# Programmer_Board_v1.net
KiCad netlist of a schematic drawn in EAGLE
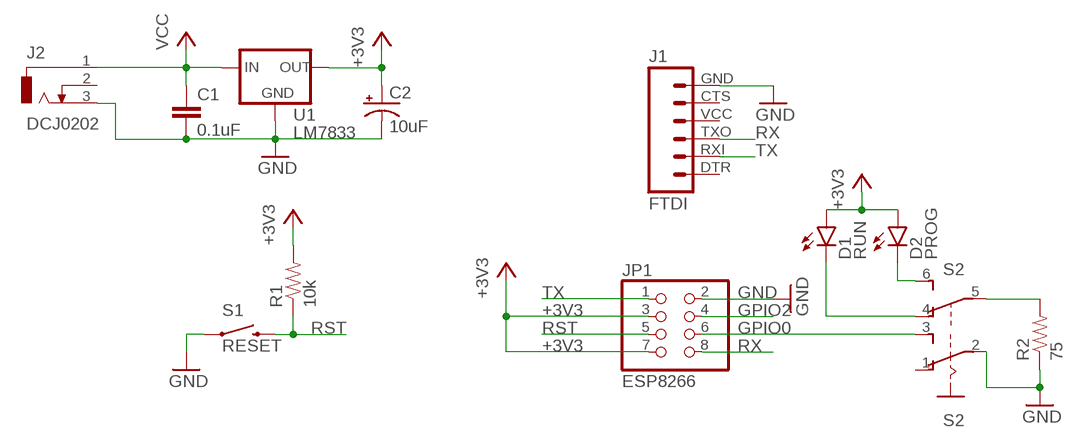
[diagram p0: schematic, sheet 1]

(export (version "E")
  (design (tool "Eeschema 10.0.6"))
  (components
    (comp (ref "C1")
      (value "0.1uF")
      (footprint "eagle-import:CAP-PTH-SMALL-KIT")
      (libsource (lib "eagle-import") (part "0.1UF-50V-20%(PTH)KIT-EZ"))
    )
    (comp (ref "C2")
      (value "10uF")
      (footprint "eagle-import:CPOL-RADIAL-10UF-25V-KIT")
      (libsource (lib "eagle-import") (part "10UF-25V-20%(PTH)KIT"))
    )
    (comp (ref "D1")
      (value "RUN")
      (footprint "eagle-import:LED3MM")
      (libsource (lib "eagle-import") (part "LED3MM"))
    )
    (comp (ref "D2")
      (value "PROG")
      (footprint "eagle-import:LED3MM")
      (libsource (lib "eagle-import") (part "LED3MM"))
    )
    (comp (ref "J1")
      (value "FTDI")
      (footprint "eagle-import:FTDI_BASIC")
      (libsource (lib "eagle-import") (part "FTDI_BASICPTH"))
    )
    (comp (ref "J2")
      (value "DCJ0202")
      (footprint "eagle-import:DCJ0202")
      (libsource (lib "eagle-import") (part "DCJ0202"))
    )
    (comp (ref "JP1")
      (value "ESP8266")
      (footprint "eagle-import:2X04")
      (libsource (lib "eagle-import") (part "PINHD-2X4"))
    )
    (comp (ref "R1")
      (value "10k")
      (footprint "eagle-import:AXIAL-0.3")
      (libsource (lib "eagle-import") (part "10KOHM-1/4W-1%(PTH)HORIZ"))
    )
    (comp (ref "R2")
      (value "75")
      (footprint "eagle-import:AXIAL-0.3")
      (libsource (lib "eagle-import") (part "10KOHM-1/4W-1%(PTH)HORIZ"))
    )
    (comp (ref "S1")
      (value "RESET")
      (footprint "eagle-import:TACTILE-PTH")
      (libsource (lib "eagle-import") (part "SWITCH-MOMENTARY-2PTH"))
    )
    (comp (ref "S2")
      (value "A68-A31")
      (footprint "eagle-import:A68-A31")
      (libsource (lib "eagle-import") (part "A68-A31"))
    )
    (comp (ref "U1")
      (value "LM7833")
      (footprint "eagle-import:TO-220-ALT")
      (libsource (lib "eagle-import") (part "V_REG_78XX-TO-220"))
    )
  )
  (nets
    (net (code "1") (name "+3V3") (class "Default")
      (node (ref "C2") (pin "1") (pinfunction "+_1") (pintype "passive"))
      (node (ref "D1") (pin "A") (pinfunction "A_A") (pintype "passive"))
      (node (ref "D2") (pin "A") (pinfunction "A_A") (pintype "passive"))
      (node (ref "JP1") (pin "3") (pinfunction "3_3") (pintype "passive"))
      (node (ref "JP1") (pin "7") (pinfunction "7_7") (pintype "passive"))
      (node (ref "R1") (pin "P$2") (pinfunction "2_P$2") (pintype "passive"))
      (node (ref "U1") (pin "OUT") (pinfunction "OUT_OUT") (pintype "passive"))
    )
    (net (code "2") (name "/GPIO0") (class "Default")
      (node (ref "JP1") (pin "6") (pinfunction "6_6") (pintype "passive"))
      (node (ref "S2") (pin "3") (pinfunction "S_3") (pintype "passive"))
    )
    (net (code "3") (name "/GPIO2") (class "Default")
      (node (ref "JP1") (pin "4") (pinfunction "4_4") (pintype "passive"))
    )
    (net (code "4") (name "/RST") (class "Default")
      (node (ref "JP1") (pin "5") (pinfunction "5_5") (pintype "passive"))
      (node (ref "R1") (pin "P$1") (pinfunction "1_P$1") (pintype "passive"))
      (node (ref "S1") (pin "3") (pinfunction "2_3") (pintype "passive"))
    )
    (net (code "5") (name "/RX") (class "Default")
      (node (ref "J1") (pin "TXO") (pinfunction "3_TXO") (pintype "passive"))
      (node (ref "JP1") (pin "8") (pinfunction "8_8") (pintype "passive"))
    )
    (net (code "6") (name "/TX") (class "Default")
      (node (ref "J1") (pin "RXI") (pinfunction "2_RXI") (pintype "passive"))
      (node (ref "JP1") (pin "1") (pinfunction "1_1") (pintype "passive"))
    )
    (net (code "7") (name "GND") (class "Default")
      (node (ref "C1") (pin "2") (pinfunction "2_2") (pintype "passive"))
      (node (ref "C2") (pin "2") (pinfunction "-_2") (pintype "passive"))
      (node (ref "J1") (pin "GND") (pinfunction "6_GND") (pintype "passive"))
      (node (ref "J2") (pin "3") (pinfunction "3_3") (pintype "passive"))
      (node (ref "JP1") (pin "2") (pinfunction "2_2") (pintype "passive"))
      (node (ref "R2") (pin "P$1") (pinfunction "1_P$1") (pintype "passive"))
      (node (ref "S1") (pin "1") (pinfunction "1_1") (pintype "passive"))
      (node (ref "S2") (pin "2") (pinfunction "P_2") (pintype "passive"))
      (node (ref "U1") (pin "GND") (pinfunction "GND_GND") (pintype "input"))
    )
    (net (code "8") (name "Net-(D1-C)") (class "Default")
      (node (ref "D1") (pin "K") (pinfunction "C_K") (pintype "passive"))
      (node (ref "S2") (pin "4") (pinfunction "O_4") (pintype "passive"))
    )
    (net (code "9") (name "Net-(D2-C)") (class "Default")
      (node (ref "D2") (pin "K") (pinfunction "C_K") (pintype "passive"))
      (node (ref "S2") (pin "6") (pinfunction "S_6") (pintype "passive"))
    )
    (net (code "10") (name "Net-(R2-2)") (class "Default")
      (node (ref "R2") (pin "P$2") (pinfunction "2_P$2") (pintype "passive"))
      (node (ref "S2") (pin "5") (pinfunction "P_5") (pintype "passive"))
    )
    (net (code "11") (name "VCC") (class "Default")
      (node (ref "C1") (pin "1") (pinfunction "1_1") (pintype "passive"))
      (node (ref "J2") (pin "1") (pinfunction "1_1") (pintype "passive"))
      (node (ref "U1") (pin "IN") (pinfunction "IN_IN") (pintype "input"))
    )
    (net (code "12") (name "unconnected-(J1-1-PadDTR)") (class "Default")
      (node (ref "J1") (pin "DTR") (pinfunction "1_DTR") (pintype "passive"))
    )
    (net (code "13") (name "unconnected-(J1-4-PadVCC)") (class "Default")
      (node (ref "J1") (pin "VCC") (pinfunction "4_VCC") (pintype "passive"))
    )
    (net (code "14") (name "unconnected-(J1-5-PadCTS)") (class "Default")
      (node (ref "J1") (pin "CTS") (pinfunction "5_CTS") (pintype "passive"))
    )
    (net (code "15") (name "unconnected-(J2-Pad2)") (class "Default")
      (node (ref "J2") (pin "2") (pinfunction "2_2") (pintype "passive"))
    )
    (net (code "16") (name "unconnected-(S2A-O-Pad1)") (class "Default")
      (node (ref "S2") (pin "1") (pinfunction "O_1") (pintype "passive"))
    )
  )
)
